# PRINCIPAL.net
KiCad netlist of a schematic drawn in Altium Designer
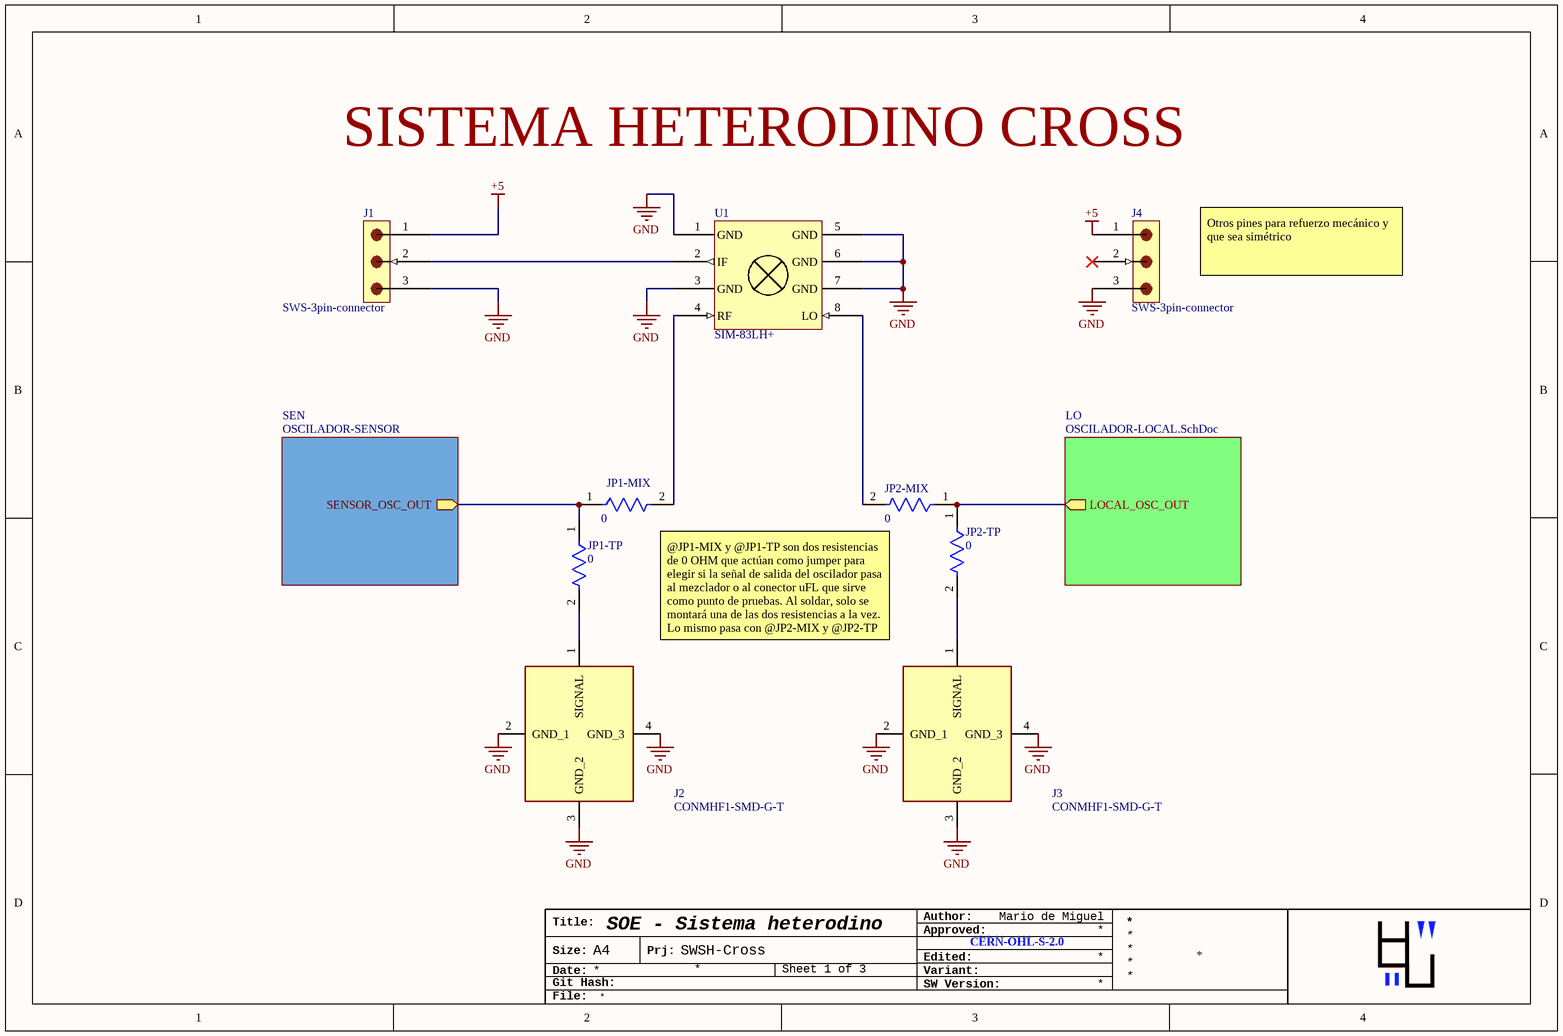
[diagram p0: PRINCIPAL.SchDoc]

(export (version "E")
  (design (tool "Eeschema 10.0.6"))
  (components
    (comp (ref "J1")
      (value "SWS-3pin-connector")
      (footprint "CASTELLATED-SWS-3PIN-CONN")
      (libsource (lib "Connectors") (part "SWS-3pin-connector"))
    )
    (comp (ref "J2")
      (value "CONMHF1-SMD-G-T")
      (footprint "SamacSys:CONMHF1SMDGT")
      (description "Integrated Circuit")
      (fields (field (name "MOUSER PART NUMBER") "712-CONMHF1-SMD-G-T"))
      (libsource (lib "*") (part "CONMHF1-SMD-G-T"))
    )
    (comp (ref "J3")
      (value "CONMHF1-SMD-G-T")
      (footprint "SamacSys:CONMHF1SMDGT")
      (description "Integrated Circuit")
      (fields (field (name "MOUSER PART NUMBER") "712-CONMHF1-SMD-G-T"))
      (libsource (lib "*") (part "CONMHF1-SMD-G-T"))
    )
    (comp (ref "J4")
      (value "SWS-3pin-connector")
      (footprint "CASTELLATED-SWS-3PIN-CONN")
      (libsource (lib "") (part "SWS-3pin-connector_1"))
    )
    (comp (ref "JP1-MIX")
      (value "0")
      (footprint "FP-CRCW0603-C-MFG")
      (description "RES 0 OHM JUMPER 1/10W 0603")
      (libsource (lib "Altium Content Vault") (part "1029c3af85768c4190bb7ad29bc67b5"))
    )
    (comp (ref "JP1-TP")
      (value "0")
      (footprint "FP-CRCW0603-C-MFG")
      (description "RES 0 OHM JUMPER 1/10W 0603")
      (libsource (lib "Altium Content Vault") (part "1029c3af85768c4190bb7ad29bc67b5"))
    )
    (comp (ref "JP2-MIX")
      (value "0")
      (footprint "FP-CRCW0603-C-MFG")
      (description "RES 0 OHM JUMPER 1/10W 0603")
      (libsource (lib "Altium Content Vault") (part "1029c3af85768c4190bb7ad29bc67b5"))
    )
    (comp (ref "JP2-TP")
      (value "0")
      (footprint "FP-CRCW0603-C-MFG")
      (description "RES 0 OHM JUMPER 1/10W 0603")
      (libsource (lib "Altium Content Vault") (part "1029c3af85768c4190bb7ad29bc67b5"))
    )
    (comp (ref "U1")
      (value "SIM-83LH+")
      (footprint "HV1195-SIM-83LH+")
      (description "RF Mixer 1700 - 8000 MHz")
      (libsource (lib "SIM-83LH+") (part "SIM-83LH+"))
    )
  )
  (nets
    (net (code "1") (name "+5") (class "Default")
      (node (ref "J1") (pin "1") (pinfunction "5V_1") (pintype "power_in"))
      (node (ref "J4") (pin "1") (pinfunction "5V_1") (pintype "power_in"))
    )
    (net (code "2") (name "/LOCAL_OSC_OUT") (class "Default")
      (node (ref "JP2-MIX") (pin "1") (pinfunction "1_1") (pintype "passive"))
      (node (ref "JP2-TP") (pin "1") (pinfunction "1_1") (pintype "passive"))
    )
    (net (code "3") (name "/SENSOR_OSC_OUT") (class "Default")
      (node (ref "JP1-MIX") (pin "1") (pinfunction "1_1") (pintype "passive"))
      (node (ref "JP1-TP") (pin "1") (pinfunction "1_1") (pintype "passive"))
    )
    (net (code "4") (name "GND") (class "Default")
      (node (ref "J1") (pin "3") (pinfunction "GND_3") (pintype "power_in"))
      (node (ref "J2") (pin "2") (pinfunction "GND_1_2") (pintype "passive"))
      (node (ref "J2") (pin "3") (pinfunction "GND_2_3") (pintype "passive"))
      (node (ref "J2") (pin "4") (pinfunction "GND_3_4") (pintype "passive"))
      (node (ref "J3") (pin "2") (pinfunction "GND_1_2") (pintype "passive"))
      (node (ref "J3") (pin "3") (pinfunction "GND_2_3") (pintype "passive"))
      (node (ref "J3") (pin "4") (pinfunction "GND_3_4") (pintype "passive"))
      (node (ref "J4") (pin "3") (pinfunction "GND_3") (pintype "power_in"))
      (node (ref "U1") (pin "1") (pinfunction "GND_1") (pintype "power_in"))
      (node (ref "U1") (pin "3") (pinfunction "GND_3") (pintype "power_in"))
      (node (ref "U1") (pin "5") (pinfunction "GND_5") (pintype "power_in"))
      (node (ref "U1") (pin "6") (pinfunction "GND_6") (pintype "power_in"))
      (node (ref "U1") (pin "7") (pinfunction "GND_7") (pintype "power_in"))
    )
    (net (code "5") (name "Net-(J1-OUT)") (class "Default")
      (node (ref "J1") (pin "2") (pinfunction "OUT_2") (pintype "input"))
      (node (ref "U1") (pin "2") (pinfunction "IF_2") (pintype "output"))
    )
    (net (code "6") (name "Net-(J2-SIGNAL)") (class "Default")
      (node (ref "J2") (pin "1") (pinfunction "SIGNAL_1") (pintype "passive"))
      (node (ref "JP1-TP") (pin "2") (pinfunction "2_2") (pintype "passive"))
    )
    (net (code "7") (name "Net-(J3-SIGNAL)") (class "Default")
      (node (ref "J3") (pin "1") (pinfunction "SIGNAL_1") (pintype "passive"))
      (node (ref "JP2-TP") (pin "2") (pinfunction "2_2") (pintype "passive"))
    )
    (net (code "8") (name "Net-(U1-LO)") (class "Default")
      (node (ref "JP2-MIX") (pin "2") (pinfunction "2_2") (pintype "passive"))
      (node (ref "U1") (pin "8") (pinfunction "LO_8") (pintype "input"))
    )
    (net (code "9") (name "Net-(U1-RF)") (class "Default")
      (node (ref "JP1-MIX") (pin "2") (pinfunction "2_2") (pintype "passive"))
      (node (ref "U1") (pin "4") (pinfunction "RF_4") (pintype "input"))
    )
    (net (code "10") (name "unconnected-(J4-OUT-Pad2)") (class "Default")
      (node (ref "J4") (pin "2") (pinfunction "OUT_2") (pintype "input+no_connect"))
    )
  )
)
